# table4.net
KiCad netlist of a schematic drawn in EasyEDA
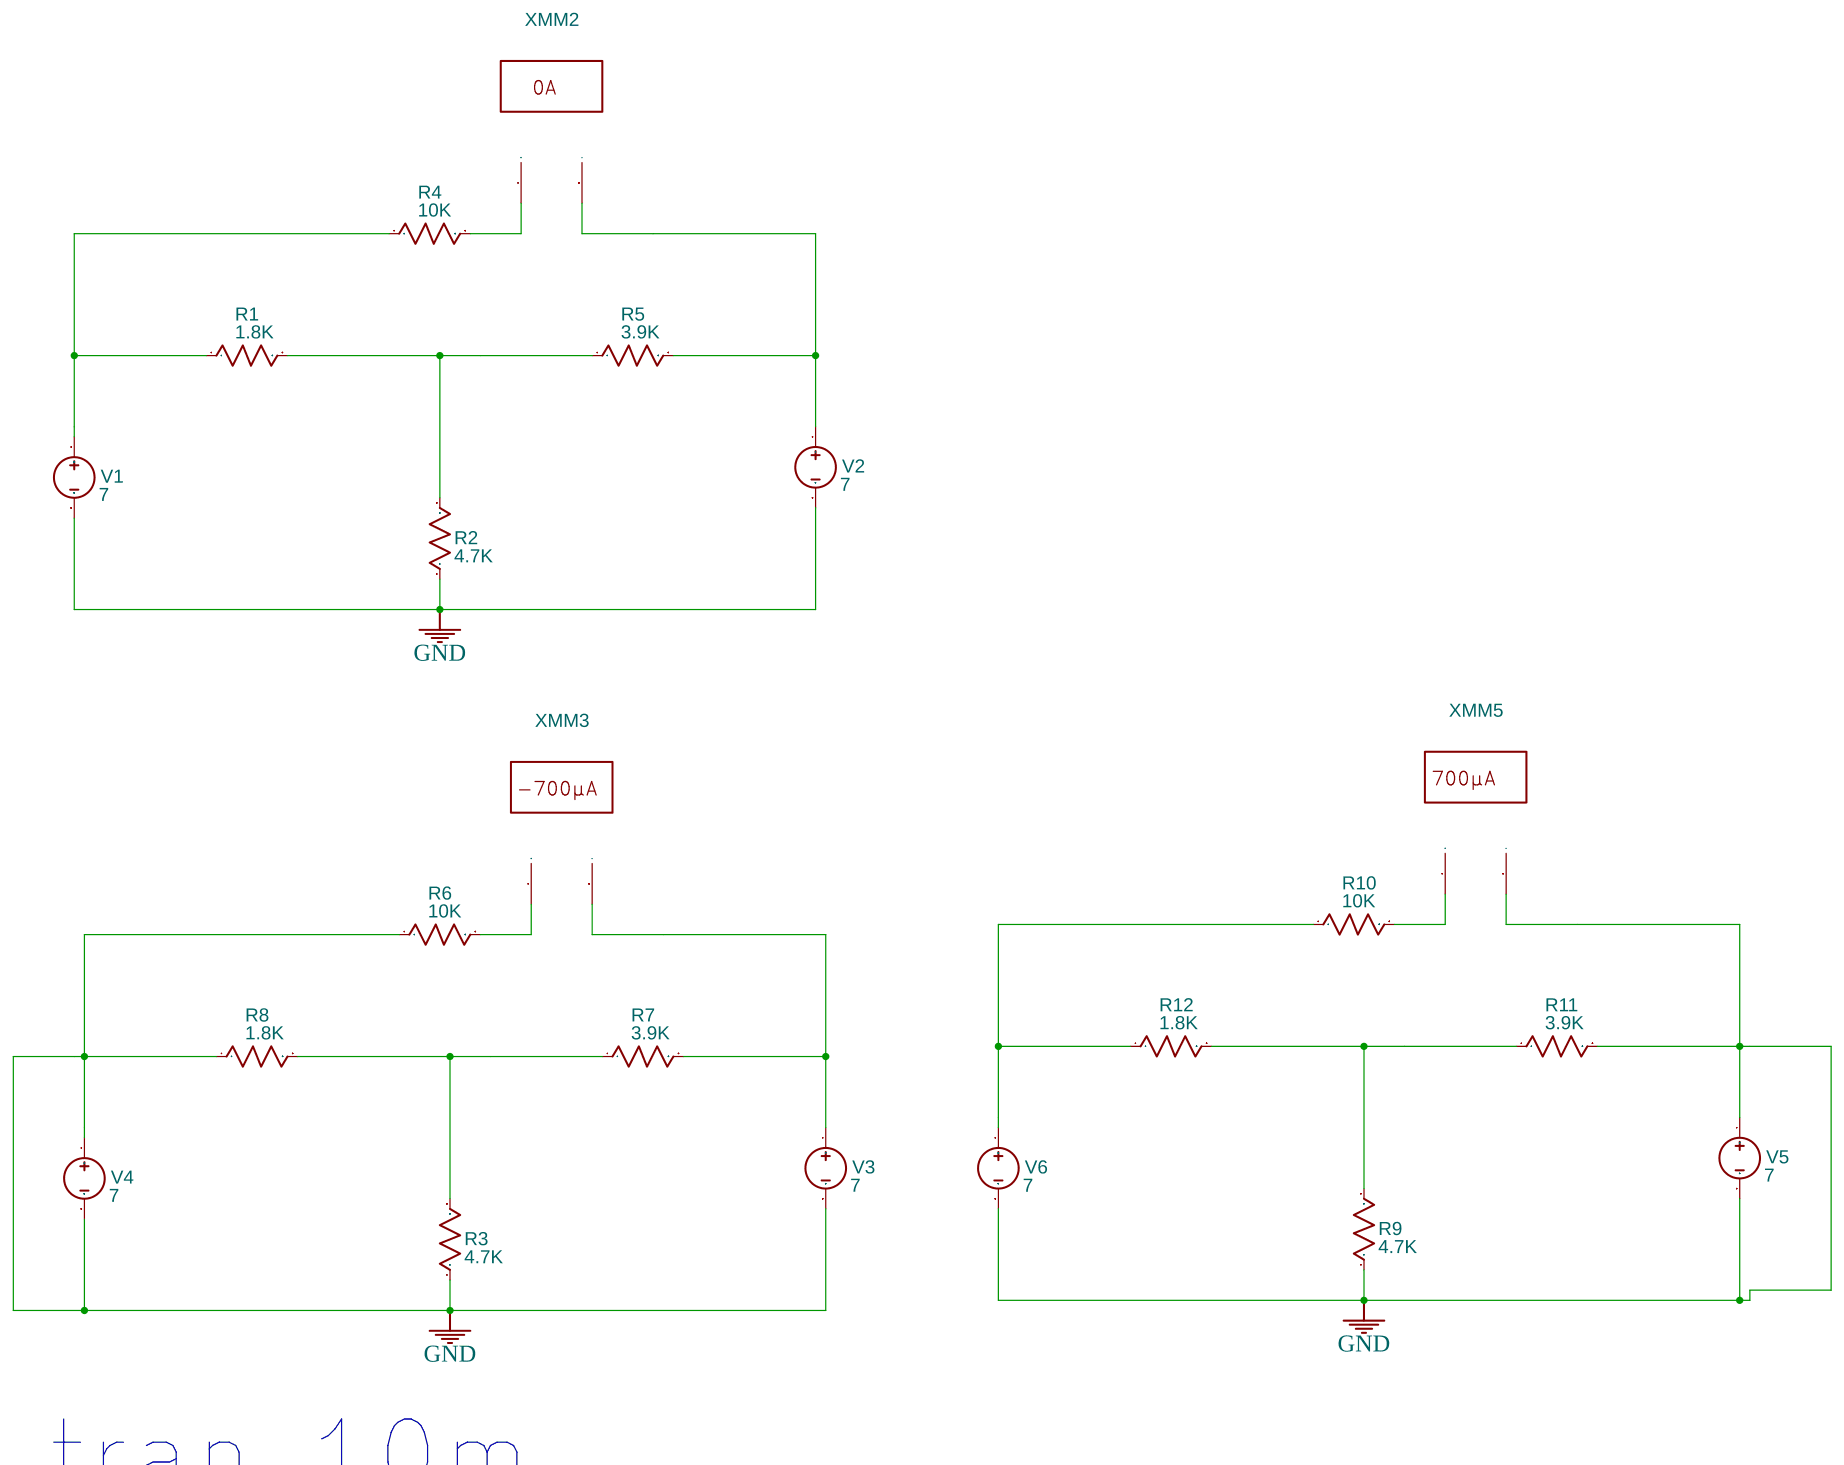
[diagram p0: schematic sheet]

(export (version "E")
  (design (tool "Eeschema 10.0.6"))
  (components
    (comp (ref "R1") (value "1.8K") (libsource (lib "") (part "Resistor_US")))
    (comp (ref "R2") (value "4.7K") (libsource (lib "") (part "Resistor_US_1")))
    (comp (ref "R3") (value "4.7K") (libsource (lib "") (part "Resistor_US_1")))
    (comp (ref "R4") (value "10K") (libsource (lib "") (part "Resistor_US")))
    (comp (ref "R5") (value "3.9K") (libsource (lib "") (part "Resistor_US")))
    (comp (ref "R6") (value "10K") (libsource (lib "") (part "Resistor_US")))
    (comp (ref "R7") (value "3.9K") (libsource (lib "") (part "Resistor_US")))
    (comp (ref "R8") (value "1.8K") (libsource (lib "") (part "Resistor_US")))
    (comp (ref "R9") (value "4.7K") (libsource (lib "") (part "Resistor_US_1")))
    (comp (ref "R10") (value "10K") (libsource (lib "") (part "Resistor_US")))
    (comp (ref "R11") (value "3.9K") (libsource (lib "") (part "Resistor_US")))
    (comp (ref "R12") (value "1.8K") (libsource (lib "") (part "Resistor_US")))
    (comp (ref "V1") (value "7") (libsource (lib "") (part "VDC")))
    (comp (ref "V2") (value "7") (libsource (lib "") (part "VDC")))
    (comp (ref "V3") (value "7") (libsource (lib "") (part "VDC")))
    (comp (ref "V4") (value "7") (libsource (lib "") (part "VDC")))
    (comp (ref "V5") (value "7") (libsource (lib "") (part "VDC")))
    (comp (ref "V6") (value "7") (libsource (lib "") (part "VDC")))
    (comp (ref "XMM2") (value "Multimeter") (libsource (lib "") (part "MULTIMETER_1")))
    (comp (ref "XMM3") (value "Multimeter") (libsource (lib "") (part "MULTIMETER")))
    (comp (ref "XMM5") (value "Multimeter") (libsource (lib "") (part "MULTIMETER_2")))
  )
  (nets
    (net (code "1") (name "GND") (class "Default")
      (node (ref "R11") (pin "2") (pinfunction "2_2") (pintype "unspecified"))
      (node (ref "R2") (pin "1") (pinfunction "1_1") (pintype "unspecified"))
      (node (ref "R3") (pin "1") (pinfunction "1_1") (pintype "unspecified"))
      (node (ref "R6") (pin "1") (pinfunction "1_1") (pintype "unspecified"))
      (node (ref "R8") (pin "1") (pinfunction "1_1") (pintype "unspecified"))
      (node (ref "R9") (pin "1") (pinfunction "1_1") (pintype "unspecified"))
      (node (ref "V1") (pin "2") (pinfunction "2_2") (pintype "unspecified"))
      (node (ref "V2") (pin "2") (pinfunction "2_2") (pintype "unspecified"))
      (node (ref "V3") (pin "2") (pinfunction "2_2") (pintype "unspecified"))
      (node (ref "V4") (pin "1") (pinfunction "1_1") (pintype "unspecified"))
      (node (ref "V4") (pin "2") (pinfunction "2_2") (pintype "unspecified"))
      (node (ref "V5") (pin "1") (pinfunction "1_1") (pintype "unspecified"))
      (node (ref "V5") (pin "2") (pinfunction "2_2") (pintype "unspecified"))
      (node (ref "V6") (pin "2") (pinfunction "2_2") (pintype "unspecified"))
      (node (ref "XMM5") (pin "2") (pinfunction "I_2") (pintype "unspecified"))
    )
    (net (code "2") (name "Net-(R1-Pad1)") (class "Default")
      (node (ref "R1") (pin "1") (pinfunction "1_1") (pintype "unspecified"))
      (node (ref "R4") (pin "1") (pinfunction "1_1") (pintype "unspecified"))
      (node (ref "V1") (pin "1") (pinfunction "1_1") (pintype "unspecified"))
    )
    (net (code "3") (name "Net-(R1-Pad2)") (class "Default")
      (node (ref "R1") (pin "2") (pinfunction "2_2") (pintype "unspecified"))
      (node (ref "R2") (pin "2") (pinfunction "2_2") (pintype "unspecified"))
      (node (ref "R5") (pin "1") (pinfunction "1_1") (pintype "unspecified"))
    )
    (net (code "4") (name "Net-(R3-Pad2)") (class "Default")
      (node (ref "R3") (pin "2") (pinfunction "2_2") (pintype "unspecified"))
      (node (ref "R7") (pin "1") (pinfunction "1_1") (pintype "unspecified"))
      (node (ref "R8") (pin "2") (pinfunction "2_2") (pintype "unspecified"))
    )
    (net (code "5") (name "Net-(R10-Pad1)") (class "Default")
      (node (ref "R10") (pin "1") (pinfunction "1_1") (pintype "unspecified"))
      (node (ref "R12") (pin "1") (pinfunction "1_1") (pintype "unspecified"))
      (node (ref "V6") (pin "1") (pinfunction "1_1") (pintype "unspecified"))
    )
    (net (code "6") (name "Net-(R11-Pad1)") (class "Default")
      (node (ref "R11") (pin "1") (pinfunction "1_1") (pintype "unspecified"))
      (node (ref "R12") (pin "2") (pinfunction "2_2") (pintype "unspecified"))
      (node (ref "R9") (pin "2") (pinfunction "2_2") (pintype "unspecified"))
    )
    (net (code "7") (name "Net-(XMM2-+)") (class "Default")
      (node (ref "R4") (pin "2") (pinfunction "2_2") (pintype "unspecified"))
      (node (ref "XMM2") (pin "1") (pinfunction "+_1") (pintype "unspecified"))
    )
    (net (code "8") (name "Net-(XMM2-I)") (class "Default")
      (node (ref "R5") (pin "2") (pinfunction "2_2") (pintype "unspecified"))
      (node (ref "V2") (pin "1") (pinfunction "1_1") (pintype "unspecified"))
      (node (ref "XMM2") (pin "2") (pinfunction "I_2") (pintype "unspecified"))
    )
    (net (code "9") (name "Net-(XMM3-+)") (class "Default")
      (node (ref "R6") (pin "2") (pinfunction "2_2") (pintype "unspecified"))
      (node (ref "XMM3") (pin "1") (pinfunction "+_1") (pintype "unspecified"))
    )
    (net (code "10") (name "Net-(XMM3-I)") (class "Default")
      (node (ref "R7") (pin "2") (pinfunction "2_2") (pintype "unspecified"))
      (node (ref "V3") (pin "1") (pinfunction "1_1") (pintype "unspecified"))
      (node (ref "XMM3") (pin "2") (pinfunction "I_2") (pintype "unspecified"))
    )
    (net (code "11") (name "Net-(XMM5-+)") (class "Default")
      (node (ref "R10") (pin "2") (pinfunction "2_2") (pintype "unspecified"))
      (node (ref "XMM5") (pin "1") (pinfunction "+_1") (pintype "unspecified"))
    )
  )
)
